# master_carconnector.net
KiCad netlist of a schematic drawn in EAGLE
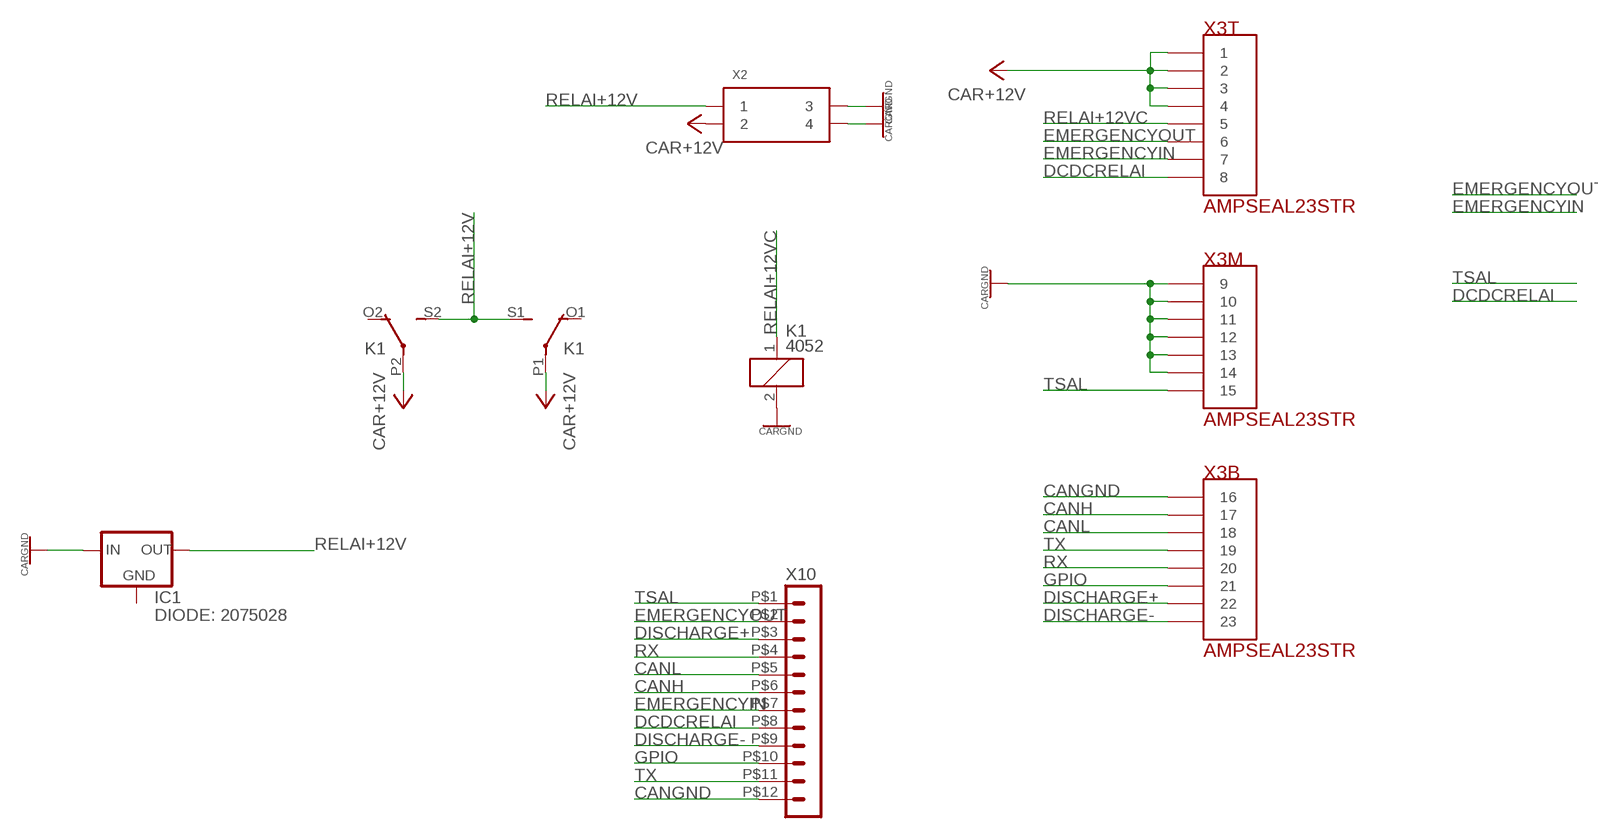
[diagram p0: schematic, sheet 1]

(export (version "E")
  (design (tool "Eeschema 10.0.6"))
  (components
    (comp (ref "IC1")
      (value "DIODE: 2075028")
      (footprint "eagle-import:TO252")
      (libsource (lib "eagle-import") (part "LM1117TO252"))
    )
    (comp (ref "K1")
      (value "4052")
      (footprint "eagle-import:F4052")
      (libsource (lib "eagle-import") (part "4052"))
    )
    (comp (ref "X2")
      (value "MINI-FIT-JR-045566")
      (footprint "eagle-import:5566-04")
      (libsource (lib "eagle-import") (part "MINI-FIT-JR-045566"))
    )
    (comp (ref "X3")
      (value "AMPSEAL23STR")
      (footprint "eagle-import:AMPSEAL23-STR")
      (libsource (lib "eagle-import") (part "AMPSEAL23STR"))
    )
    (comp (ref "X10")
      (value "HEADER_POS12_43045-1212")
      (footprint "eagle-import:43045-1212")
      (libsource (lib "eagle-import") (part "HEADER_POS12_?43045-1212"))
    )
  )
  (nets
    (net (code "1") (name "/CANGND") (class "Default")
      (node (ref "X10") (pin "P$12") (pinfunction "12_P$12") (pintype "passive"))
      (node (ref "X3") (pin "P$16") (pinfunction "16_P$16") (pintype "bidirectional"))
    )
    (net (code "2") (name "/CANH") (class "Default")
      (node (ref "X10") (pin "P$6") (pinfunction "6_P$6") (pintype "passive"))
      (node (ref "X3") (pin "P$17") (pinfunction "17_P$17") (pintype "bidirectional"))
    )
    (net (code "3") (name "/CANL") (class "Default")
      (node (ref "X10") (pin "P$5") (pinfunction "5_P$5") (pintype "passive"))
      (node (ref "X3") (pin "P$18") (pinfunction "18_P$18") (pintype "bidirectional"))
    )
    (net (code "4") (name "/DCDCRELAI") (class "Default")
      (node (ref "X10") (pin "P$8") (pinfunction "8_P$8") (pintype "passive"))
      (node (ref "X3") (pin "P$8") (pinfunction "8_P$8") (pintype "bidirectional"))
    )
    (net (code "5") (name "/DISCHARGE+") (class "Default")
      (node (ref "X10") (pin "P$3") (pinfunction "3_P$3") (pintype "passive"))
      (node (ref "X3") (pin "P$22") (pinfunction "22_P$22") (pintype "bidirectional"))
    )
    (net (code "6") (name "/DISCHARGE-") (class "Default")
      (node (ref "X10") (pin "P$9") (pinfunction "9_P$9") (pintype "passive"))
      (node (ref "X3") (pin "P$23") (pinfunction "23_P$23") (pintype "bidirectional"))
    )
    (net (code "7") (name "/EMERGENCYIN") (class "Default")
      (node (ref "X10") (pin "P$7") (pinfunction "7_P$7") (pintype "passive"))
      (node (ref "X3") (pin "P$7") (pinfunction "7_P$7") (pintype "bidirectional"))
    )
    (net (code "8") (name "/EMERGENCYOUT") (class "Default")
      (node (ref "X10") (pin "P$2") (pinfunction "2_P$2") (pintype "passive"))
      (node (ref "X3") (pin "P$6") (pinfunction "6_P$6") (pintype "bidirectional"))
    )
    (net (code "9") (name "/GPIO") (class "Default")
      (node (ref "X10") (pin "P$10") (pinfunction "10_P$10") (pintype "passive"))
      (node (ref "X3") (pin "P$21") (pinfunction "21_P$21") (pintype "bidirectional"))
    )
    (net (code "10") (name "/RELAI+12V") (class "Default")
      (node (ref "IC1") (pin "3") (pinfunction "OUT_3") (pintype "passive"))
      (node (ref "K1") (pin "S1") (pinfunction "S_S1") (pintype "passive"))
      (node (ref "K1") (pin "S2") (pinfunction "S_S2") (pintype "passive"))
      (node (ref "X2") (pin "P1") (pinfunction "1_P1") (pintype "bidirectional"))
    )
    (net (code "11") (name "/RELAI+12VC") (class "Default")
      (node (ref "K1") (pin "1") (pinfunction "1_1") (pintype "passive"))
      (node (ref "X3") (pin "P$5") (pinfunction "5_P$5") (pintype "bidirectional"))
    )
    (net (code "12") (name "/RX") (class "Default")
      (node (ref "X10") (pin "P$4") (pinfunction "4_P$4") (pintype "passive"))
      (node (ref "X3") (pin "P$20") (pinfunction "20_P$20") (pintype "bidirectional"))
    )
    (net (code "13") (name "/TSAL") (class "Default")
      (node (ref "X10") (pin "P$1") (pinfunction "1_P$1") (pintype "passive"))
      (node (ref "X3") (pin "P$15") (pinfunction "15_P$15") (pintype "bidirectional"))
    )
    (net (code "14") (name "/TX") (class "Default")
      (node (ref "X10") (pin "P$11") (pinfunction "11_P$11") (pintype "passive"))
      (node (ref "X3") (pin "P$19") (pinfunction "19_P$19") (pintype "bidirectional"))
    )
    (net (code "15") (name "CAR+12V") (class "Default")
      (node (ref "K1") (pin "P1") (pinfunction "P_P1") (pintype "passive"))
      (node (ref "K1") (pin "P2") (pinfunction "P_P2") (pintype "passive"))
      (node (ref "X2") (pin "P2") (pinfunction "2_P2") (pintype "bidirectional"))
      (node (ref "X3") (pin "P$1") (pinfunction "1_P$1") (pintype "bidirectional"))
      (node (ref "X3") (pin "P$2") (pinfunction "2_P$2") (pintype "bidirectional"))
      (node (ref "X3") (pin "P$3") (pinfunction "3_P$3") (pintype "bidirectional"))
      (node (ref "X3") (pin "P$4") (pinfunction "4_P$4") (pintype "bidirectional"))
    )
    (net (code "16") (name "CARGND") (class "Default")
      (node (ref "IC1") (pin "2") (pinfunction "IN_2") (pintype "input"))
      (node (ref "K1") (pin "2") (pinfunction "2_2") (pintype "passive"))
      (node (ref "X2") (pin "P3") (pinfunction "3_P3") (pintype "bidirectional"))
      (node (ref "X2") (pin "P4") (pinfunction "4_P4") (pintype "bidirectional"))
      (node (ref "X3") (pin "P$10") (pinfunction "10_P$10") (pintype "bidirectional"))
      (node (ref "X3") (pin "P$11") (pinfunction "11_P$11") (pintype "bidirectional"))
      (node (ref "X3") (pin "P$12") (pinfunction "12_P$12") (pintype "bidirectional"))
      (node (ref "X3") (pin "P$13") (pinfunction "13_P$13") (pintype "bidirectional"))
      (node (ref "X3") (pin "P$14") (pinfunction "14_P$14") (pintype "bidirectional"))
      (node (ref "X3") (pin "P$9") (pinfunction "9_P$9") (pintype "bidirectional"))
    )
    (net (code "17") (name "unconnected-(IC1-GND-Pad1)") (class "Default")
      (node (ref "IC1") (pin "1") (pinfunction "GND_1") (pintype "input"))
    )
    (net (code "18") (name "unconnected-(K1B-O-PadO1)") (class "Default")
      (node (ref "K1") (pin "O1") (pinfunction "O_O1") (pintype "passive"))
    )
    (net (code "19") (name "unconnected-(K1C-O-PadO2)") (class "Default")
      (node (ref "K1") (pin "O2") (pinfunction "O_O2") (pintype "passive"))
    )
  )
)
